# pfe.net
KiCad netlist of a schematic drawn in Altium Designer
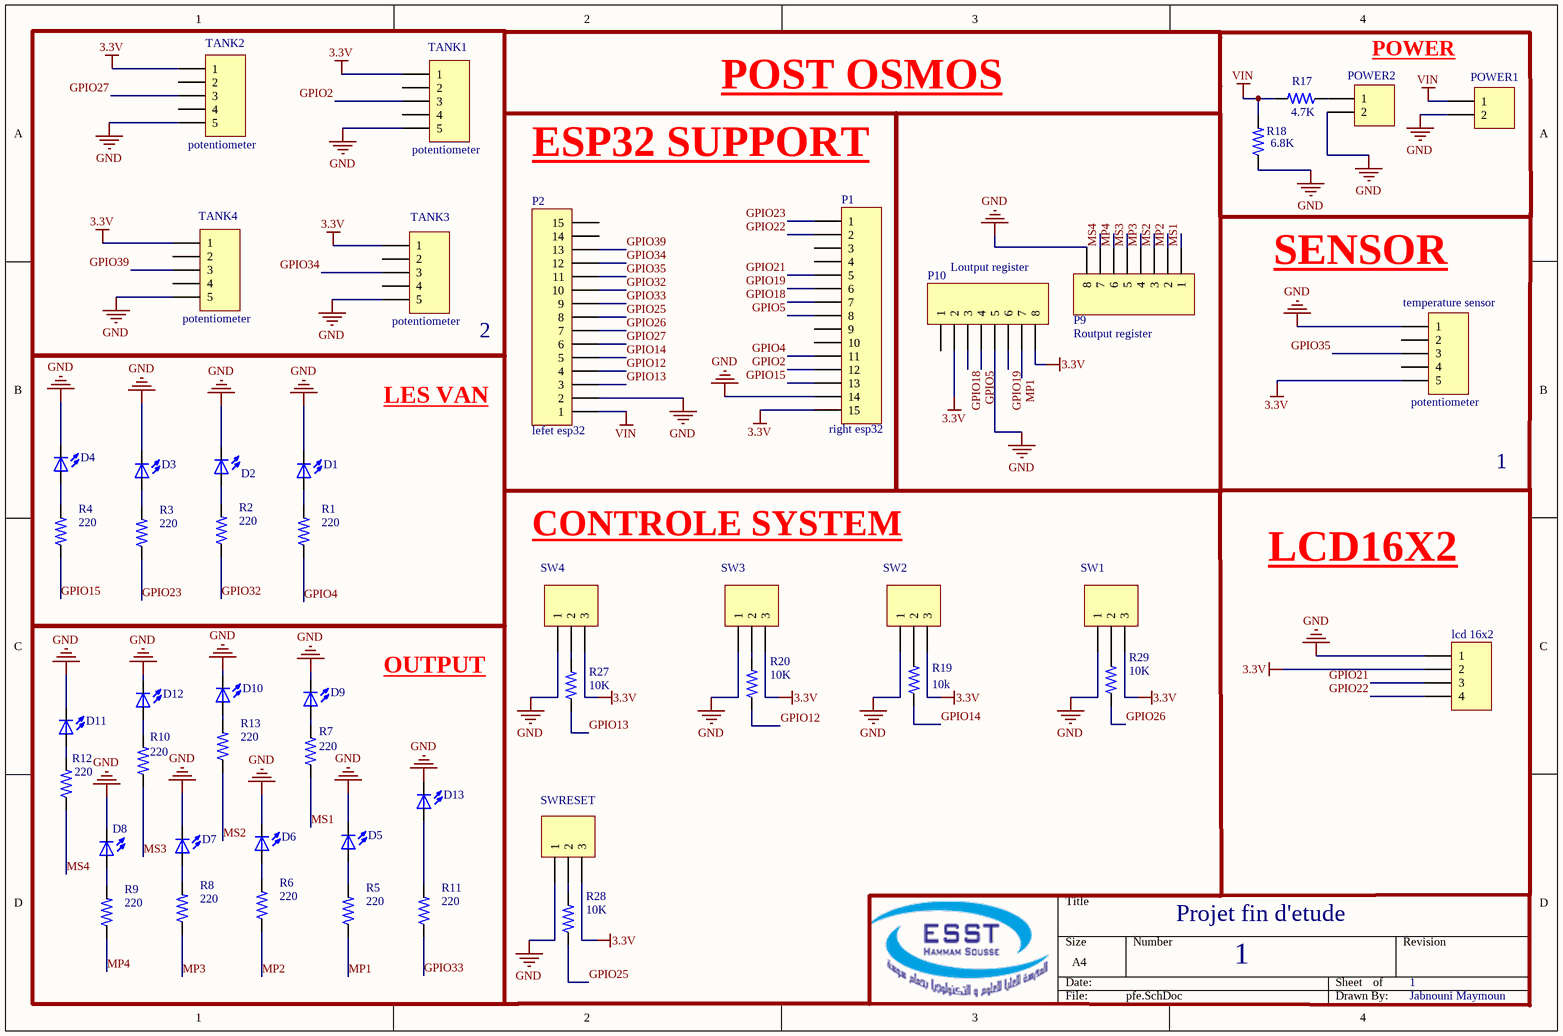
[diagram p0: pfe.SchDoc]

(export (version "E")
  (design (tool "Eeschema 10.0.6"))
  (components
    (comp (ref "D1")
      (value "~")
      (footprint "LED3MM")
      (description "Red 619nm LED Indication - Discrete 1.9V Radial")
      (fields (field (name "MF") "Vishay") (field (name "MP") "TLLR4400"))
      (libsource (lib "TLLR4400") (part "TLLR4400"))
    )
    (comp (ref "D2")
      (value "~")
      (footprint "LED3MM")
      (description "Red 619nm LED Indication - Discrete 1.9V Radial")
      (fields (field (name "MF") "Vishay") (field (name "MP") "TLLR4400"))
      (libsource (lib "TLLR4400") (part "TLLR4400"))
    )
    (comp (ref "D3")
      (value "~")
      (footprint "LED3MM")
      (description "Red 619nm LED Indication - Discrete 1.9V Radial")
      (fields (field (name "MF") "Vishay") (field (name "MP") "TLLR4400"))
      (libsource (lib "TLLR4400") (part "TLLR4400"))
    )
    (comp (ref "D4")
      (value "~")
      (footprint "LED3MM")
      (description "Red 619nm LED Indication - Discrete 1.9V Radial")
      (fields (field (name "MF") "Vishay") (field (name "MP") "TLLR4400"))
      (libsource (lib "TLLR4400") (part "TLLR4400"))
    )
    (comp (ref "D5")
      (value "~")
      (footprint "LED3MM")
      (description "Red 619nm LED Indication - Discrete 1.9V Radial")
      (fields (field (name "MF") "Vishay") (field (name "MP") "TLLR4400"))
      (libsource (lib "TLLR4400") (part "TLLR4400"))
    )
    (comp (ref "D6")
      (value "~")
      (footprint "LED3MM")
      (description "Red 619nm LED Indication - Discrete 1.9V Radial")
      (fields (field (name "MF") "Vishay") (field (name "MP") "TLLR4400"))
      (libsource (lib "TLLR4400") (part "TLLR4400"))
    )
    (comp (ref "D7")
      (value "~")
      (footprint "LED3MM")
      (description "Red 619nm LED Indication - Discrete 1.9V Radial")
      (fields (field (name "MF") "Vishay") (field (name "MP") "TLLR4400"))
      (libsource (lib "TLLR4400") (part "TLLR4400"))
    )
    (comp (ref "D8")
      (value "~")
      (footprint "LED3MM")
      (description "Red 619nm LED Indication - Discrete 1.9V Radial")
      (fields (field (name "MF") "Vishay") (field (name "MP") "TLLR4400"))
      (libsource (lib "TLLR4400") (part "TLLR4400"))
    )
    (comp (ref "D9")
      (value "~")
      (footprint "LED3MM")
      (description "Red 619nm LED Indication - Discrete 1.9V Radial")
      (fields (field (name "MF") "Vishay") (field (name "MP") "TLLR4400"))
      (libsource (lib "TLLR4400") (part "TLLR4400"))
    )
    (comp (ref "D10")
      (value "~")
      (footprint "LED3MM")
      (description "Red 619nm LED Indication - Discrete 1.9V Radial")
      (fields (field (name "MF") "Vishay") (field (name "MP") "TLLR4400"))
      (libsource (lib "TLLR4400") (part "TLLR4400"))
    )
    (comp (ref "D11")
      (value "~")
      (footprint "LED3MM")
      (description "Red 619nm LED Indication - Discrete 1.9V Radial")
      (fields (field (name "MF") "Vishay") (field (name "MP") "TLLR4400"))
      (libsource (lib "TLLR4400") (part "TLLR4400"))
    )
    (comp (ref "D12")
      (value "~")
      (footprint "LED3MM")
      (description "Red 619nm LED Indication - Discrete 1.9V Radial")
      (fields (field (name "MF") "Vishay") (field (name "MP") "TLLR4400"))
      (libsource (lib "TLLR4400") (part "TLLR4400"))
    )
    (comp (ref "D13")
      (value "~")
      (footprint "LED3MM")
      (description "Red 619nm LED Indication - Discrete 1.9V Radial")
      (fields (field (name "MF") "Vishay") (field (name "MP") "TLLR4400"))
      (libsource (lib "TLLR4400") (part "TLLR4400"))
    )
    (comp (ref "lcd 16x2")
      (value "lcd 16x2")
      (footprint "HDR1X4")
      (description "Header, 4-Pin")
      (fields (field (name "PUBLISHER") "Altium Limited"))
      (libsource (lib "Miscellaneous Connectors") (part "Header 4"))
    )
    (comp (ref "P1")
      (value "right esp32")
      (footprint "HDR1X15")
      (description "Header, 15-Pin")
      (fields (field (name "PUBLISHER") "Altium Limited"))
      (libsource (lib "Miscellaneous Connectors") (part "Header 15"))
    )
    (comp (ref "P2")
      (value "lefet esp32")
      (footprint "HDR1X15")
      (description "Header, 15-Pin")
      (fields (field (name "PUBLISHER") "Altium Limited"))
      (libsource (lib "") (part "Header 15_1"))
    )
    (comp (ref "P9")
      (value "Routput register")
      (footprint "HDR1X8")
      (description "Header, 8-Pin")
      (fields (field (name "PUBLISHER") "Altium Limited"))
      (libsource (lib "Miscellaneous Connectors") (part "Header 8"))
    )
    (comp (ref "P10")
      (value "Loutput register")
      (footprint "HDR1X8")
      (description "Header, 8-Pin")
      (fields (field (name "PUBLISHER") "Altium Limited"))
      (libsource (lib "") (part "Header 8_1"))
    )
    (comp (ref "POWER1")
      (value "POWER1")
      (footprint "HDR1X2")
      (description "Header, 2-Pin")
      (fields (field (name "PUBLISHER") "Altium Limited"))
      (libsource (lib "Miscellaneous Connectors") (part "Header 2"))
    )
    (comp (ref "POWER2")
      (value "POWER2")
      (footprint "HDR1X2")
      (description "Header, 2-Pin")
      (fields (field (name "PUBLISHER") "Altium Limited"))
      (libsource (lib "Miscellaneous Connectors") (part "Header 2"))
    )
    (comp (ref "R1")
      (value "220")
      (footprint "RESAD640W45L370D200")
      (description "LR0204 1% 220R")
      (fields (field (name "MP") "1622194-1"))
      (libsource (lib "1622194-1 (1)") (part "1622194-1"))
    )
    (comp (ref "R2")
      (value "220")
      (footprint "RESAD640W45L370D200")
      (description "LR0204 1% 220R")
      (fields (field (name "MP") "1622194-1"))
      (libsource (lib "1622194-1 (1)") (part "1622194-1"))
    )
    (comp (ref "R3")
      (value "220")
      (footprint "RESAD640W45L370D200")
      (description "LR0204 1% 220R")
      (fields (field (name "MP") "1622194-1"))
      (libsource (lib "1622194-1 (1)") (part "1622194-1"))
    )
    (comp (ref "R4")
      (value "220")
      (footprint "RESAD640W45L370D200")
      (description "LR0204 1% 220R")
      (fields (field (name "MP") "1622194-1"))
      (libsource (lib "1622194-1 (1)") (part "1622194-1"))
    )
    (comp (ref "R5")
      (value "220")
      (footprint "RESAD640W45L370D200")
      (description "LR0204 1% 220R")
      (fields (field (name "MP") "1622194-1"))
      (libsource (lib "1622194-1 (1)") (part "1622194-1"))
    )
    (comp (ref "R6")
      (value "220")
      (footprint "RESAD640W45L370D200")
      (description "LR0204 1% 220R")
      (fields (field (name "MP") "1622194-1"))
      (libsource (lib "1622194-1 (1)") (part "1622194-1"))
    )
    (comp (ref "R7")
      (value "220")
      (footprint "RESAD640W45L370D200")
      (description "LR0204 1% 220R")
      (fields (field (name "MP") "1622194-1"))
      (libsource (lib "1622194-1 (1)") (part "1622194-1"))
    )
    (comp (ref "R8")
      (value "220")
      (footprint "RESAD640W45L370D200")
      (description "LR0204 1% 220R")
      (fields (field (name "MP") "1622194-1"))
      (libsource (lib "1622194-1 (1)") (part "1622194-1"))
    )
    (comp (ref "R9")
      (value "220")
      (footprint "RESAD640W45L370D200")
      (description "LR0204 1% 220R")
      (fields (field (name "MP") "1622194-1"))
      (libsource (lib "1622194-1 (1)") (part "1622194-1"))
    )
    (comp (ref "R10")
      (value "220")
      (footprint "RESAD640W45L370D200")
      (description "LR0204 1% 220R")
      (fields (field (name "MP") "1622194-1"))
      (libsource (lib "1622194-1 (1)") (part "1622194-1"))
    )
    (comp (ref "R11")
      (value "220")
      (footprint "RESAD640W45L370D200")
      (description "LR0204 1% 220R")
      (fields (field (name "MP") "1622194-1"))
      (libsource (lib "1622194-1 (1)") (part "1622194-1"))
    )
    (comp (ref "R12")
      (value "220")
      (footprint "RESAD640W45L370D200")
      (description "LR0204 1% 220R")
      (fields (field (name "MP") "1622194-1"))
      (libsource (lib "1622194-1 (1)") (part "1622194-1"))
    )
    (comp (ref "R13")
      (value "220")
      (footprint "RESAD640W45L370D200")
      (description "LR0204 1% 220R")
      (fields (field (name "MP") "1622194-1"))
      (libsource (lib "1622194-1 (1)") (part "1622194-1"))
    )
    (comp (ref "R17")
      (value "4.7K")
      (footprint "RESAD640W45L370D200")
      (description "LR0204 1% 220R")
      (fields (field (name "MP") "1622194-1"))
      (libsource (lib "1622194-1 (1)") (part "1622194-1"))
    )
    (comp (ref "R18")
      (value "6.8K")
      (footprint "RESAD640W45L370D200")
      (description "LR0204 1% 220R")
      (fields (field (name "MP") "1622194-1"))
      (libsource (lib "1622194-1 (1)") (part "1622194-1"))
    )
    (comp (ref "R19")
      (value "10k")
      (footprint "RESAD640W45L370D200")
      (description "LR0204 1% 220R")
      (fields (field (name "MP") "1622194-1"))
      (libsource (lib "1622194-1 (1)") (part "1622194-1"))
    )
    (comp (ref "R20")
      (value "10K")
      (footprint "RESAD640W45L370D200")
      (description "LR0204 1% 220R")
      (fields (field (name "MP") "1622194-1"))
      (libsource (lib "1622194-1 (1)") (part "1622194-1"))
    )
    (comp (ref "R27")
      (value "10K")
      (footprint "RESAD640W45L370D200")
      (description "LR0204 1% 220R")
      (fields (field (name "MP") "1622194-1"))
      (libsource (lib "1622194-1 (1)") (part "1622194-1"))
    )
    (comp (ref "R28")
      (value "10K")
      (footprint "RESAD640W45L370D200")
      (description "LR0204 1% 220R")
      (fields (field (name "MP") "1622194-1"))
      (libsource (lib "1622194-1 (1)") (part "1622194-1"))
    )
    (comp (ref "R29")
      (value "10K")
      (footprint "RESAD640W45L370D200")
      (description "LR0204 1% 220R")
      (fields (field (name "MP") "1622194-1"))
      (libsource (lib "1622194-1 (1)") (part "1622194-1"))
    )
    (comp (ref "SW1")
      (value "SW1")
      (footprint "HDR1X3")
      (description "Header, 3-Pin")
      (fields (field (name "PUBLISHER") "Altium Limited"))
      (libsource (lib "Miscellaneous Connectors") (part "Header 3"))
    )
    (comp (ref "SW2")
      (value "SW2")
      (footprint "HDR1X3")
      (description "Header, 3-Pin")
      (fields (field (name "PUBLISHER") "Altium Limited"))
      (libsource (lib "Miscellaneous Connectors") (part "Header 3"))
    )
    (comp (ref "SW3")
      (value "SW3")
      (footprint "HDR1X3")
      (description "Header, 3-Pin")
      (fields (field (name "PUBLISHER") "Altium Limited"))
      (libsource (lib "Miscellaneous Connectors") (part "Header 3"))
    )
    (comp (ref "SW4")
      (value "SW4")
      (footprint "HDR1X3")
      (description "Header, 3-Pin")
      (fields (field (name "PUBLISHER") "Altium Limited"))
      (libsource (lib "Miscellaneous Connectors") (part "Header 3"))
    )
    (comp (ref "SWRESET")
      (value "SWRESET")
      (footprint "HDR1X3")
      (description "Header, 3-Pin")
      (fields (field (name "PUBLISHER") "Altium Limited"))
      (libsource (lib "Miscellaneous Connectors") (part "Header 3"))
    )
    (comp (ref "TANK1")
      (value "potentiometer")
      (footprint "HDR1X5")
      (description "Header, 5-Pin")
      (fields (field (name "PUBLISHER") "Altium Limited"))
      (libsource (lib "Miscellaneous Connectors") (part "Header 5"))
    )
    (comp (ref "TANK2")
      (value "potentiometer")
      (footprint "HDR1X5")
      (description "Header, 5-Pin")
      (fields (field (name "PUBLISHER") "Altium Limited"))
      (libsource (lib "Miscellaneous Connectors") (part "Header 5"))
    )
    (comp (ref "TANK3")
      (value "potentiometer")
      (footprint "HDR1X5")
      (description "Header, 5-Pin")
      (fields (field (name "PUBLISHER") "Altium Limited"))
      (libsource (lib "Miscellaneous Connectors") (part "Header 5"))
    )
    (comp (ref "TANK4")
      (value "potentiometer")
      (footprint "HDR1X5")
      (description "Header, 5-Pin")
      (fields (field (name "PUBLISHER") "Altium Limited"))
      (libsource (lib "Miscellaneous Connectors") (part "Header 5"))
    )
    (comp (ref "temperature sensor")
      (value "potentiometer")
      (footprint "HDR1X5")
      (description "Header, 5-Pin")
      (fields (field (name "PUBLISHER") "Altium Limited"))
      (libsource (lib "Miscellaneous Connectors") (part "Header 5"))
    )
  )
  (nets
    (net (code "1") (name "/GPIO2") (class "Default")
      (node (ref "P1") (pin "12") (pinfunction "12_12") (pintype "passive"))
      (node (ref "TANK1") (pin "3") (pinfunction "3_3") (pintype "passive"))
    )
    (net (code "2") (name "/GPIO4") (class "Default")
      (node (ref "P1") (pin "11") (pinfunction "11_11") (pintype "passive"))
      (node (ref "R1") (pin "1") (pinfunction "1_1") (pintype "passive"))
    )
    (net (code "3") (name "/GPIO5") (class "Default")
      (node (ref "P1") (pin "8") (pinfunction "8_8") (pintype "passive"))
      (node (ref "P10") (pin "4") (pinfunction "4_4") (pintype "passive"))
    )
    (net (code "4") (name "/GPIO12") (class "Default")
      (node (ref "P2") (pin "4") (pinfunction "4_4") (pintype "passive"))
      (node (ref "R20") (pin "1") (pinfunction "1_1") (pintype "passive"))
    )
    (net (code "5") (name "/GPIO13") (class "Default")
      (node (ref "P2") (pin "3") (pinfunction "3_3") (pintype "passive"))
      (node (ref "R27") (pin "1") (pinfunction "1_1") (pintype "passive"))
    )
    (net (code "6") (name "/GPIO14") (class "Default")
      (node (ref "P2") (pin "5") (pinfunction "5_5") (pintype "passive"))
      (node (ref "R19") (pin "1") (pinfunction "1_1") (pintype "passive"))
    )
    (net (code "7") (name "/GPIO15") (class "Default")
      (node (ref "P1") (pin "13") (pinfunction "13_13") (pintype "passive"))
      (node (ref "R4") (pin "1") (pinfunction "1_1") (pintype "passive"))
    )
    (net (code "8") (name "/GPIO18") (class "Default")
      (node (ref "P1") (pin "7") (pinfunction "7_7") (pintype "passive"))
      (node (ref "P10") (pin "3") (pinfunction "3_3") (pintype "passive"))
    )
    (net (code "9") (name "/GPIO19") (class "Default")
      (node (ref "P1") (pin "6") (pinfunction "6_6") (pintype "passive"))
      (node (ref "P10") (pin "6") (pinfunction "6_6") (pintype "passive"))
    )
    (net (code "10") (name "/GPIO21") (class "Default")
      (node (ref "P1") (pin "5") (pinfunction "5_5") (pintype "passive"))
      (node (ref "lcd 16x2") (pin "3") (pinfunction "3_3") (pintype "passive"))
    )
    (net (code "11") (name "/GPIO22") (class "Default")
      (node (ref "P1") (pin "2") (pinfunction "2_2") (pintype "passive"))
      (node (ref "lcd 16x2") (pin "4") (pinfunction "4_4") (pintype "passive"))
    )
    (net (code "12") (name "/GPIO23") (class "Default")
      (node (ref "P1") (pin "1") (pinfunction "1_1") (pintype "passive"))
      (node (ref "R3") (pin "1") (pinfunction "1_1") (pintype "passive"))
    )
    (net (code "13") (name "/GPIO25") (class "Default")
      (node (ref "P2") (pin "8") (pinfunction "8_8") (pintype "passive"))
      (node (ref "R28") (pin "1") (pinfunction "1_1") (pintype "passive"))
    )
    (net (code "14") (name "/GPIO26") (class "Default")
      (node (ref "P2") (pin "7") (pinfunction "7_7") (pintype "passive"))
      (node (ref "R29") (pin "1") (pinfunction "1_1") (pintype "passive"))
    )
    (net (code "15") (name "/GPIO27") (class "Default")
      (node (ref "P2") (pin "6") (pinfunction "6_6") (pintype "passive"))
      (node (ref "TANK2") (pin "3") (pinfunction "3_3") (pintype "passive"))
    )
    (net (code "16") (name "/GPIO32") (class "Default")
      (node (ref "P2") (pin "10") (pinfunction "10_10") (pintype "passive"))
      (node (ref "R2") (pin "1") (pinfunction "1_1") (pintype "passive"))
    )
    (net (code "17") (name "/GPIO33") (class "Default")
      (node (ref "P2") (pin "9") (pinfunction "9_9") (pintype "passive"))
      (node (ref "R11") (pin "1") (pinfunction "1_1") (pintype "passive"))
    )
    (net (code "18") (name "/GPIO34") (class "Default")
      (node (ref "P2") (pin "12") (pinfunction "12_12") (pintype "passive"))
      (node (ref "TANK3") (pin "3") (pinfunction "3_3") (pintype "passive"))
    )
    (net (code "19") (name "/GPIO35") (class "Default")
      (node (ref "P2") (pin "11") (pinfunction "11_11") (pintype "passive"))
      (node (ref "temperature sensor") (pin "3") (pinfunction "3_3") (pintype "passive"))
    )
    (net (code "20") (name "/GPIO39") (class "Default")
      (node (ref "P2") (pin "13") (pinfunction "13_13") (pintype "passive"))
      (node (ref "TANK4") (pin "3") (pinfunction "3_3") (pintype "passive"))
    )
    (net (code "21") (name "/MP1") (class "Default")
      (node (ref "P10") (pin "7") (pinfunction "7_7") (pintype "passive"))
      (node (ref "R5") (pin "1") (pinfunction "1_1") (pintype "passive"))
    )
    (net (code "22") (name "/MP2") (class "Default")
      (node (ref "P9") (pin "2") (pinfunction "2_2") (pintype "passive"))
      (node (ref "R6") (pin "1") (pinfunction "1_1") (pintype "passive"))
    )
    (net (code "23") (name "/MP3") (class "Default")
      (node (ref "P9") (pin "4") (pinfunction "4_4") (pintype "passive"))
      (node (ref "R8") (pin "1") (pinfunction "1_1") (pintype "passive"))
    )
    (net (code "24") (name "/MP4") (class "Default")
      (node (ref "P9") (pin "6") (pinfunction "6_6") (pintype "passive"))
      (node (ref "R9") (pin "1") (pinfunction "1_1") (pintype "passive"))
    )
    (net (code "25") (name "/MS1") (class "Default")
      (node (ref "P9") (pin "1") (pinfunction "1_1") (pintype "passive"))
      (node (ref "R7") (pin "1") (pinfunction "1_1") (pintype "passive"))
    )
    (net (code "26") (name "/MS2") (class "Default")
      (node (ref "P9") (pin "3") (pinfunction "3_3") (pintype "passive"))
      (node (ref "R13") (pin "1") (pinfunction "1_1") (pintype "passive"))
    )
    (net (code "27") (name "/MS3") (class "Default")
      (node (ref "P9") (pin "5") (pinfunction "5_5") (pintype "passive"))
      (node (ref "R10") (pin "1") (pinfunction "1_1") (pintype "passive"))
    )
    (net (code "28") (name "/MS4") (class "Default")
      (node (ref "P9") (pin "7") (pinfunction "7_7") (pintype "passive"))
      (node (ref "R12") (pin "1") (pinfunction "1_1") (pintype "passive"))
    )
    (net (code "29") (name "3.3V") (class "Default")
      (node (ref "P1") (pin "15") (pinfunction "15_15") (pintype "passive"))
      (node (ref "P10") (pin "2") (pinfunction "2_2") (pintype "passive"))
      (node (ref "P10") (pin "8") (pinfunction "8_8") (pintype "passive"))
      (node (ref "SW1") (pin "3") (pinfunction "3_3") (pintype "passive"))
      (node (ref "SW2") (pin "3") (pinfunction "3_3") (pintype "passive"))
      (node (ref "SW3") (pin "3") (pinfunction "3_3") (pintype "passive"))
      (node (ref "SW4") (pin "3") (pinfunction "3_3") (pintype "passive"))
      (node (ref "SWRESET") (pin "3") (pinfunction "3_3") (pintype "passive"))
      (node (ref "TANK1") (pin "1") (pinfunction "1_1") (pintype "passive"))
      (node (ref "TANK2") (pin "1") (pinfunction "1_1") (pintype "passive"))
      (node (ref "TANK3") (pin "1") (pinfunction "1_1") (pintype "passive"))
      (node (ref "TANK4") (pin "1") (pinfunction "1_1") (pintype "passive"))
      (node (ref "lcd 16x2") (pin "2") (pinfunction "2_2") (pintype "passive"))
      (node (ref "temperature sensor") (pin "5") (pinfunction "5_5") (pintype "passive"))
    )
    (net (code "30") (name "GND") (class "Default")
      (node (ref "D1") (pin "K") (pinfunction "C_K") (pintype "passive"))
      (node (ref "D10") (pin "K") (pinfunction "C_K") (pintype "passive"))
      (node (ref "D11") (pin "K") (pinfunction "C_K") (pintype "passive"))
      (node (ref "D12") (pin "K") (pinfunction "C_K") (pintype "passive"))
      (node (ref "D13") (pin "K") (pinfunction "C_K") (pintype "passive"))
      (node (ref "D2") (pin "K") (pinfunction "C_K") (pintype "passive"))
      (node (ref "D3") (pin "K") (pinfunction "C_K") (pintype "passive"))
      (node (ref "D4") (pin "K") (pinfunction "C_K") (pintype "passive"))
      (node (ref "D5") (pin "K") (pinfunction "C_K") (pintype "passive"))
      (node (ref "D6") (pin "K") (pinfunction "C_K") (pintype "passive"))
      (node (ref "D7") (pin "K") (pinfunction "C_K") (pintype "passive"))
      (node (ref "D8") (pin "K") (pinfunction "C_K") (pintype "passive"))
      (node (ref "D9") (pin "K") (pinfunction "C_K") (pintype "passive"))
      (node (ref "P1") (pin "14") (pinfunction "14_14") (pintype "passive"))
      (node (ref "P10") (pin "5") (pinfunction "5_5") (pintype "passive"))
      (node (ref "P2") (pin "2") (pinfunction "2_2") (pintype "passive"))
      (node (ref "P9") (pin "8") (pinfunction "8_8") (pintype "passive"))
      (node (ref "POWER1") (pin "2") (pinfunction "2_2") (pintype "passive"))
      (node (ref "POWER2") (pin "2") (pinfunction "2_2") (pintype "passive"))
      (node (ref "R18") (pin "1") (pinfunction "1_1") (pintype "passive"))
      (node (ref "SW1") (pin "1") (pinfunction "1_1") (pintype "passive"))
      (node (ref "SW2") (pin "1") (pinfunction "1_1") (pintype "passive"))
      (node (ref "SW3") (pin "1") (pinfunction "1_1") (pintype "passive"))
      (node (ref "SW4") (pin "1") (pinfunction "1_1") (pintype "passive"))
      (node (ref "SWRESET") (pin "1") (pinfunction "1_1") (pintype "passive"))
      (node (ref "TANK1") (pin "5") (pinfunction "5_5") (pintype "passive"))
      (node (ref "TANK2") (pin "5") (pinfunction "5_5") (pintype "passive"))
      (node (ref "TANK3") (pin "5") (pinfunction "5_5") (pintype "passive"))
      (node (ref "TANK4") (pin "5") (pinfunction "5_5") (pintype "passive"))
      (node (ref "lcd 16x2") (pin "1") (pinfunction "1_1") (pintype "passive"))
      (node (ref "temperature sensor") (pin "1") (pinfunction "1_1") (pintype "passive"))
    )
    (net (code "31") (name "Net-(D1-PadA)") (class "Default")
      (node (ref "D1") (pin "A") (pinfunction "A_A") (pintype "passive"))
      (node (ref "R1") (pin "2") (pinfunction "2_2") (pintype "passive"))
    )
    (net (code "32") (name "Net-(D2-PadA)") (class "Default")
      (node (ref "D2") (pin "A") (pinfunction "A_A") (pintype "passive"))
      (node (ref "R2") (pin "2") (pinfunction "2_2") (pintype "passive"))
    )
    (net (code "33") (name "Net-(D3-PadA)") (class "Default")
      (node (ref "D3") (pin "A") (pinfunction "A_A") (pintype "passive"))
      (node (ref "R3") (pin "2") (pinfunction "2_2") (pintype "passive"))
    )
    (net (code "34") (name "Net-(D4-PadA)") (class "Default")
      (node (ref "D4") (pin "A") (pinfunction "A_A") (pintype "passive"))
      (node (ref "R4") (pin "2") (pinfunction "2_2") (pintype "passive"))
    )
    (net (code "35") (name "Net-(D5-PadA)") (class "Default")
      (node (ref "D5") (pin "A") (pinfunction "A_A") (pintype "passive"))
      (node (ref "R5") (pin "2") (pinfunction "2_2") (pintype "passive"))
    )
    (net (code "36") (name "Net-(D6-PadA)") (class "Default")
      (node (ref "D6") (pin "A") (pinfunction "A_A") (pintype "passive"))
      (node (ref "R6") (pin "2") (pinfunction "2_2") (pintype "passive"))
    )
    (net (code "37") (name "Net-(D7-PadA)") (class "Default")
      (node (ref "D7") (pin "A") (pinfunction "A_A") (pintype "passive"))
      (node (ref "R8") (pin "2") (pinfunction "2_2") (pintype "passive"))
    )
    (net (code "38") (name "Net-(D8-PadA)") (class "Default")
      (node (ref "D8") (pin "A") (pinfunction "A_A") (pintype "passive"))
      (node (ref "R9") (pin "2") (pinfunction "2_2") (pintype "passive"))
    )
    (net (code "39") (name "Net-(D9-PadA)") (class "Default")
      (node (ref "D9") (pin "A") (pinfunction "A_A") (pintype "passive"))
      (node (ref "R7") (pin "2") (pinfunction "2_2") (pintype "passive"))
    )
    (net (code "40") (name "Net-(D10-PadA)") (class "Default")
      (node (ref "D10") (pin "A") (pinfunction "A_A") (pintype "passive"))
      (node (ref "R13") (pin "2") (pinfunction "2_2") (pintype "passive"))
    )
    (net (code "41") (name "Net-(D11-PadA)") (class "Default")
      (node (ref "D11") (pin "A") (pinfunction "A_A") (pintype "passive"))
      (node (ref "R12") (pin "2") (pinfunction "2_2") (pintype "passive"))
    )
    (net (code "42") (name "Net-(D12-PadA)") (class "Default")
      (node (ref "D12") (pin "A") (pinfunction "A_A") (pintype "passive"))
      (node (ref "R10") (pin "2") (pinfunction "2_2") (pintype "passive"))
    )
    (net (code "43") (name "Net-(D13-PadA)") (class "Default")
      (node (ref "D13") (pin "A") (pinfunction "A_A") (pintype "passive"))
      (node (ref "R11") (pin "2") (pinfunction "2_2") (pintype "passive"))
    )
    (net (code "44") (name "Net-(POWER2-Pad1)") (class "Default")
      (node (ref "POWER2") (pin "1") (pinfunction "1_1") (pintype "passive"))
      (node (ref "R17") (pin "1") (pinfunction "1_1") (pintype "passive"))
    )
    (net (code "45") (name "Net-(R19-Pad2)") (class "Default")
      (node (ref "R19") (pin "2") (pinfunction "2_2") (pintype "passive"))
      (node (ref "SW2") (pin "2") (pinfunction "2_2") (pintype "passive"))
    )
    (net (code "46") (name "Net-(R20-Pad2)") (class "Default")
      (node (ref "R20") (pin "2") (pinfunction "2_2") (pintype "passive"))
      (node (ref "SW3") (pin "2") (pinfunction "2_2") (pintype "passive"))
    )
    (net (code "47") (name "Net-(R27-Pad2)") (class "Default")
      (node (ref "R27") (pin "2") (pinfunction "2_2") (pintype "passive"))
      (node (ref "SW4") (pin "2") (pinfunction "2_2") (pintype "passive"))
    )
    (net (code "48") (name "Net-(R28-Pad2)") (class "Default")
      (node (ref "R28") (pin "2") (pinfunction "2_2") (pintype "passive"))
      (node (ref "SWRESET") (pin "2") (pinfunction "2_2") (pintype "passive"))
    )
    (net (code "49") (name "Net-(R29-Pad2)") (class "Default")
      (node (ref "R29") (pin "2") (pinfunction "2_2") (pintype "passive"))
      (node (ref "SW1") (pin "2") (pinfunction "2_2") (pintype "passive"))
    )
    (net (code "50") (name "VIN") (class "Default")
      (node (ref "P2") (pin "1") (pinfunction "1_1") (pintype "passive"))
      (node (ref "POWER1") (pin "1") (pinfunction "1_1") (pintype "passive"))
      (node (ref "R17") (pin "2") (pinfunction "2_2") (pintype "passive"))
      (node (ref "R18") (pin "2") (pinfunction "2_2") (pintype "passive"))
    )
    (net (code "51") (name "unconnected-(P1-Pad3)") (class "Default")
      (node (ref "P1") (pin "3") (pinfunction "3_3") (pintype "passive"))
    )
    (net (code "52") (name "unconnected-(P1-Pad4)") (class "Default")
      (node (ref "P1") (pin "4") (pinfunction "4_4") (pintype "passive"))
    )
    (net (code "53") (name "unconnected-(P1-Pad9)") (class "Default")
      (node (ref "P1") (pin "9") (pinfunction "9_9") (pintype "passive"))
    )
    (net (code "54") (name "unconnected-(P1-Pad10)") (class "Default")
      (node (ref "P1") (pin "10") (pinfunction "10_10") (pintype "passive"))
    )
    (net (code "55") (name "unconnected-(P2-Pad14)") (class "Default")
      (node (ref "P2") (pin "14") (pinfunction "14_14") (pintype "passive"))
    )
    (net (code "56") (name "unconnected-(P2-Pad15)") (class "Default")
      (node (ref "P2") (pin "15") (pinfunction "15_15") (pintype "passive"))
    )
    (net (code "57") (name "unconnected-(P10-Pad1)") (class "Default")
      (node (ref "P10") (pin "1") (pinfunction "1_1") (pintype "passive"))
    )
    (net (code "58") (name "unconnected-(TANK1-Pad2)") (class "Default")
      (node (ref "TANK1") (pin "2") (pinfunction "2_2") (pintype "passive"))
    )
    (net (code "59") (name "unconnected-(TANK1-Pad4)") (class "Default")
      (node (ref "TANK1") (pin "4") (pinfunction "4_4") (pintype "passive"))
    )
    (net (code "60") (name "unconnected-(TANK2-Pad2)") (class "Default")
      (node (ref "TANK2") (pin "2") (pinfunction "2_2") (pintype "passive"))
    )
    (net (code "61") (name "unconnected-(TANK2-Pad4)") (class "Default")
      (node (ref "TANK2") (pin "4") (pinfunction "4_4") (pintype "passive"))
    )
    (net (code "62") (name "unconnected-(TANK3-Pad2)") (class "Default")
      (node (ref "TANK3") (pin "2") (pinfunction "2_2") (pintype "passive"))
    )
    (net (code "63") (name "unconnected-(TANK3-Pad4)") (class "Default")
      (node (ref "TANK3") (pin "4") (pinfunction "4_4") (pintype "passive"))
    )
    (net (code "64") (name "unconnected-(TANK4-Pad2)") (class "Default")
      (node (ref "TANK4") (pin "2") (pinfunction "2_2") (pintype "passive"))
    )
    (net (code "65") (name "unconnected-(TANK4-Pad4)") (class "Default")
      (node (ref "TANK4") (pin "4") (pinfunction "4_4") (pintype "passive"))
    )
    (net (code "66") (name "unconnected-(temperature sensor-Pad2)") (class "Default")
      (node (ref "temperature sensor") (pin "2") (pinfunction "2_2") (pintype "passive"))
    )
    (net (code "67") (name "unconnected-(temperature sensor-Pad4)") (class "Default")
      (node (ref "temperature sensor") (pin "4") (pinfunction "4_4") (pintype "passive"))
    )
  )
)
